# Sheet1.net
KiCad netlist of a schematic drawn in Altium Designer
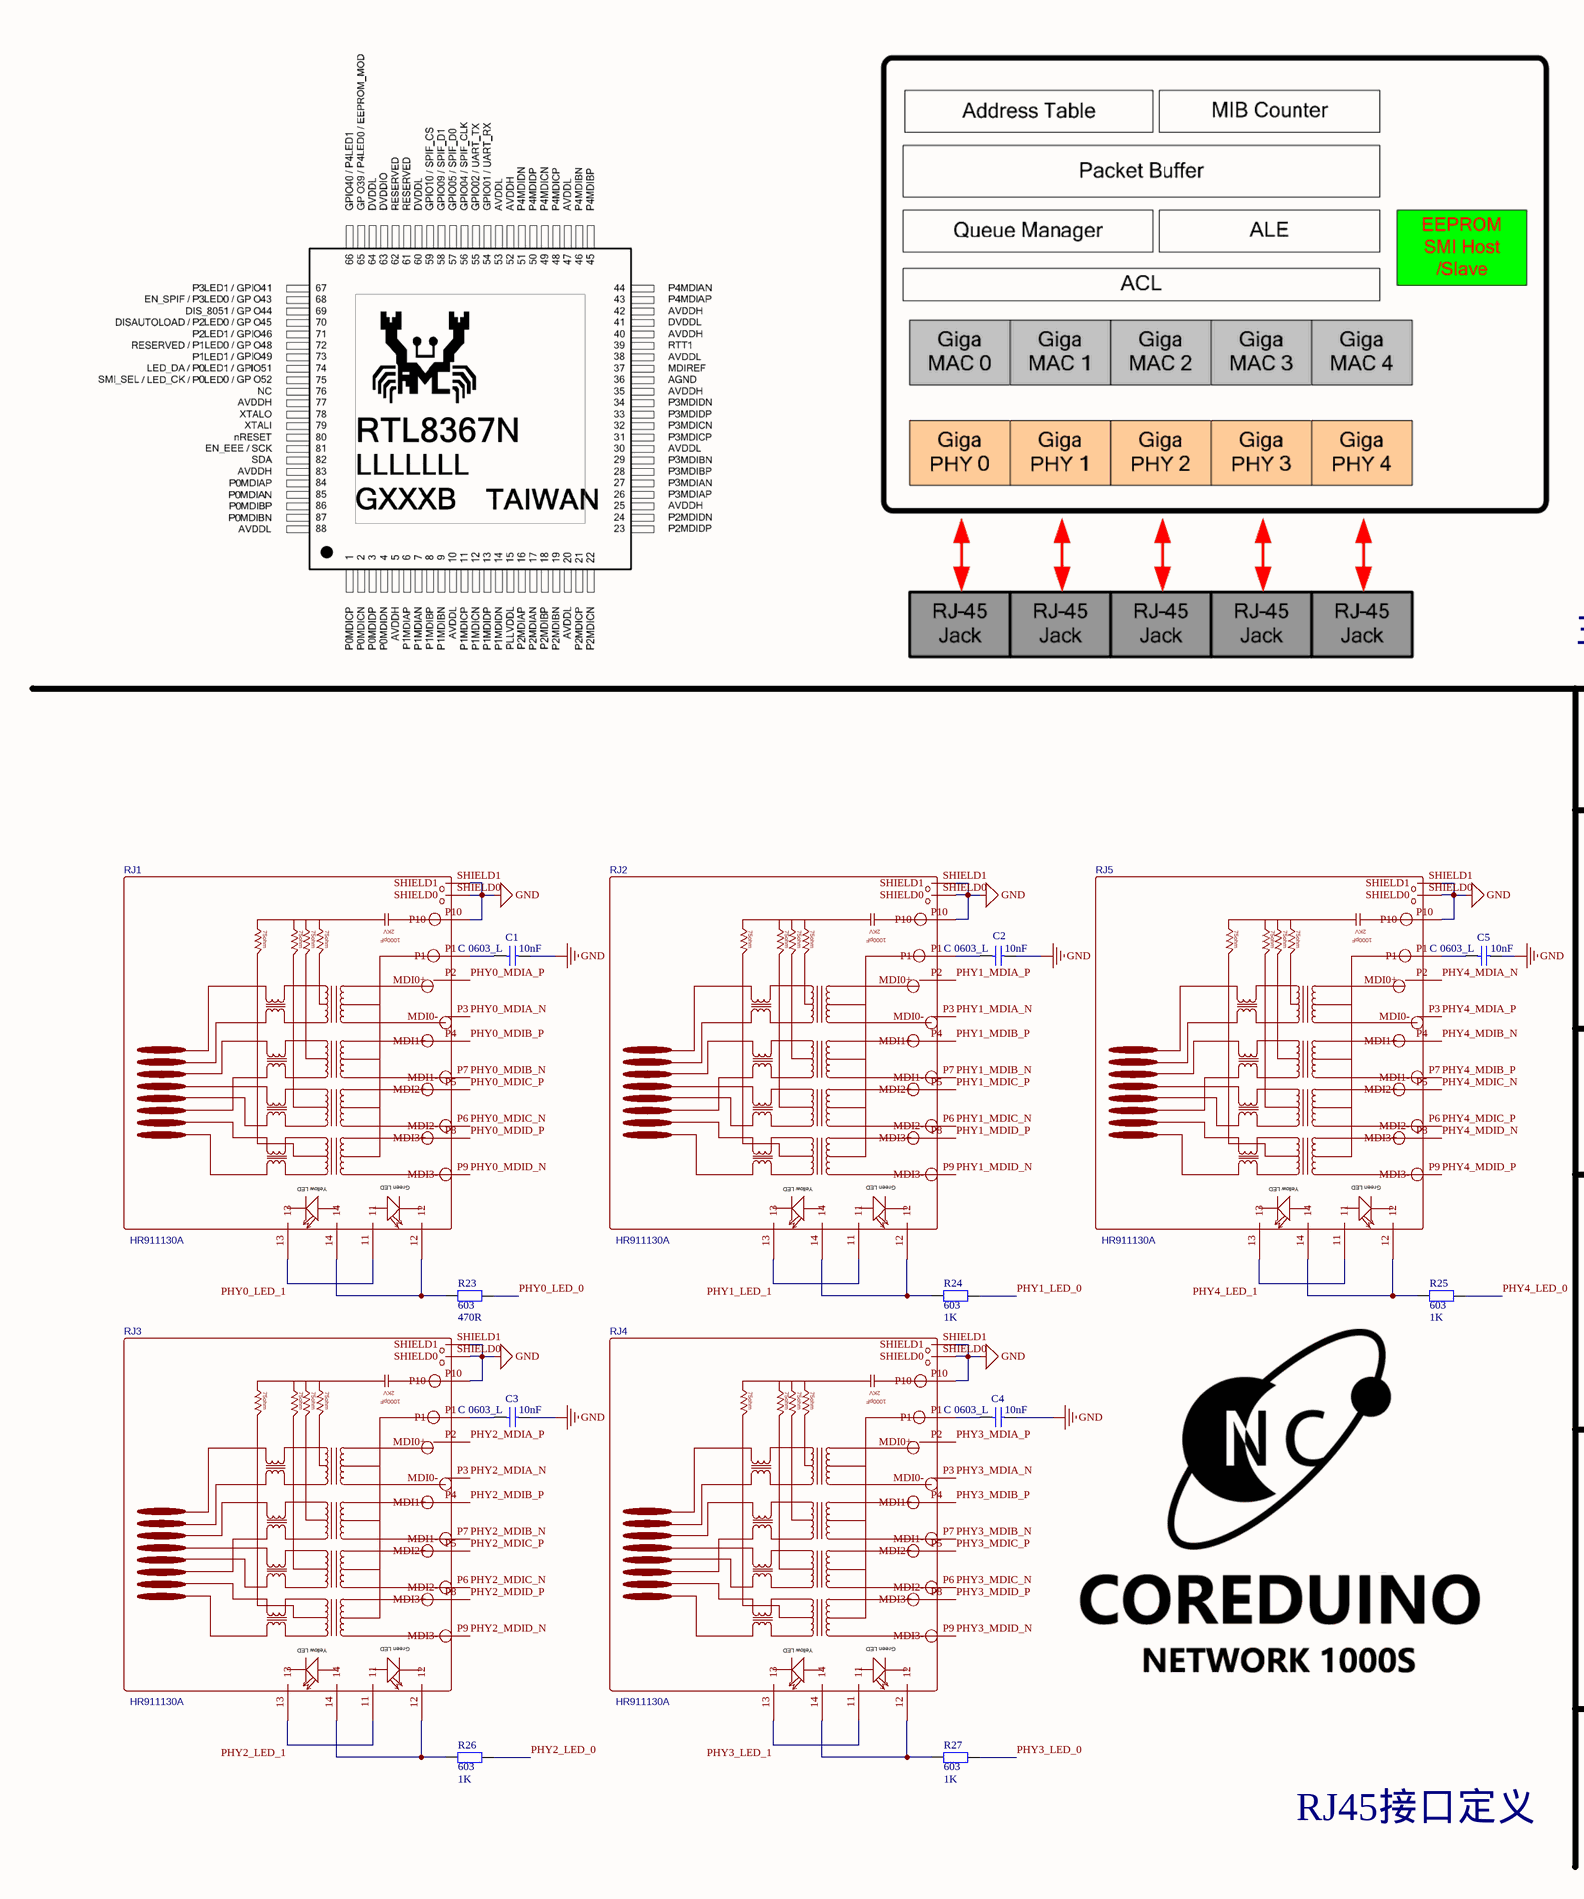
[diagram p0: Sheet1.SchDoc, left]
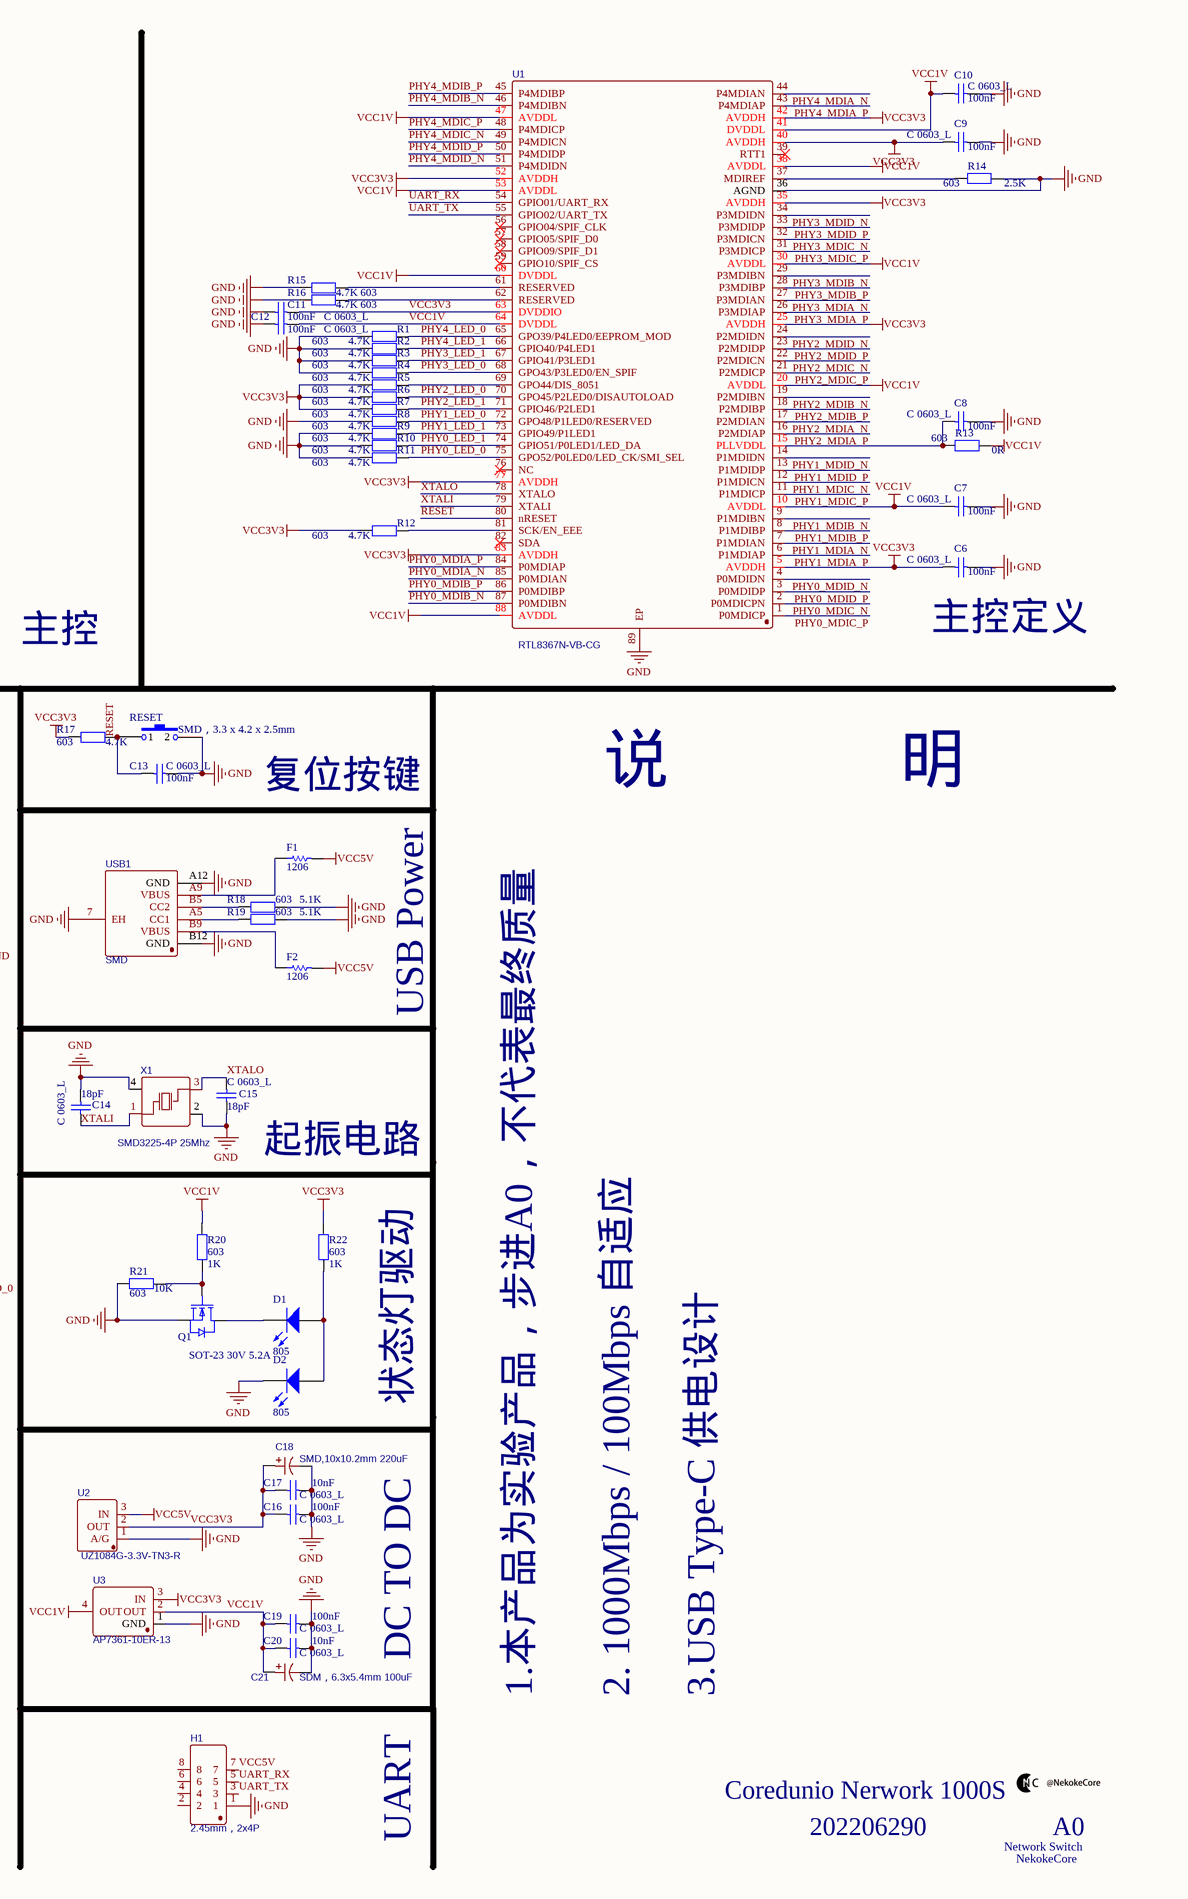
[diagram p1: Sheet1.SchDoc, right]

(export (version "E")
  (design (tool "Eeschema 10.0.6"))
  (components
    (comp (ref "C1")
      (value "C 0603_L")
      (footprint "C 0603_L")
      (description "贴片电容器（Capacitor）")
      (fields (field (name "ALTIUM_VALUE") "10nF") (field (name "PUBLISHER") "Altium Limited"))
      (libsource (lib "BaseLib") (part "C 0603_L"))
    )
    (comp (ref "C2")
      (value "C 0603_L")
      (footprint "C 0603_L")
      (description "贴片电容器（Capacitor）")
      (fields (field (name "ALTIUM_VALUE") "10nF") (field (name "PUBLISHER") "Altium Limited"))
      (libsource (lib "BaseLib") (part "C 0603_L"))
    )
    (comp (ref "C3")
      (value "C 0603_L")
      (footprint "C 0603_L")
      (description "贴片电容器（Capacitor）")
      (fields (field (name "ALTIUM_VALUE") "10nF") (field (name "PUBLISHER") "Altium Limited"))
      (libsource (lib "BaseLib") (part "C 0603_L"))
    )
    (comp (ref "C4")
      (value "C 0603_L")
      (footprint "C 0603_L")
      (description "贴片电容器（Capacitor）")
      (fields (field (name "ALTIUM_VALUE") "10nF") (field (name "PUBLISHER") "Altium Limited"))
      (libsource (lib "BaseLib") (part "C 0603_L"))
    )
    (comp (ref "C5")
      (value "C 0603_L")
      (footprint "C 0603_L")
      (description "贴片电容器（Capacitor）")
      (fields (field (name "ALTIUM_VALUE") "10nF") (field (name "PUBLISHER") "Altium Limited"))
      (libsource (lib "BaseLib") (part "C 0603_L"))
    )
    (comp (ref "C6")
      (value "C 0603_L")
      (footprint "C 0603_L")
      (description "贴片电容器（Capacitor）")
      (fields (field (name "ALTIUM_VALUE") "100nF") (field (name "PUBLISHER") "Altium Limited"))
      (libsource (lib "BaseLib") (part "C 0603_L"))
    )
    (comp (ref "C7")
      (value "C 0603_L")
      (footprint "C 0603_L")
      (description "贴片电容器（Capacitor）")
      (fields (field (name "ALTIUM_VALUE") "100nF") (field (name "PUBLISHER") "Altium Limited"))
      (libsource (lib "BaseLib") (part "C 0603_L"))
    )
    (comp (ref "C8")
      (value "C 0603_L")
      (footprint "C 0603_L")
      (description "贴片电容器（Capacitor）")
      (fields (field (name "ALTIUM_VALUE") "100nF") (field (name "PUBLISHER") "Altium Limited"))
      (libsource (lib "BaseLib") (part "C 0603_L"))
    )
    (comp (ref "C9")
      (value "C 0603_L")
      (footprint "C 0603_L")
      (description "贴片电容器（Capacitor）")
      (fields (field (name "ALTIUM_VALUE") "100nF") (field (name "PUBLISHER") "Altium Limited"))
      (libsource (lib "BaseLib") (part "C 0603_L"))
    )
    (comp (ref "C10")
      (value "C 0603_L")
      (footprint "C 0603_L")
      (description "贴片电容器（Capacitor）")
      (fields (field (name "ALTIUM_VALUE") "100nF") (field (name "PUBLISHER") "Altium Limited"))
      (libsource (lib "BaseLib") (part "C 0603_L"))
    )
    (comp (ref "C11")
      (value "C 0603_L")
      (footprint "C 0603_L")
      (description "贴片电容器（Capacitor）")
      (fields (field (name "ALTIUM_VALUE") "100nF") (field (name "PUBLISHER") "Altium Limited"))
      (libsource (lib "BaseLib") (part "C 0603_L"))
    )
    (comp (ref "C12")
      (value "C 0603_L")
      (footprint "C 0603_L")
      (description "贴片电容器（Capacitor）")
      (fields (field (name "ALTIUM_VALUE") "100nF") (field (name "PUBLISHER") "Altium Limited"))
      (libsource (lib "BaseLib") (part "C 0603_L"))
    )
    (comp (ref "C13")
      (value "C 0603_L")
      (footprint "C 0603_L")
      (description "贴片电容器（Capacitor）")
      (fields (field (name "ALTIUM_VALUE") "100nF") (field (name "PUBLISHER") "Altium Limited"))
      (libsource (lib "BaseLib") (part "C 0603_L"))
    )
    (comp (ref "C14")
      (value "C 0603_L")
      (footprint "C 0603_L")
      (description "贴片电容器（Capacitor）")
      (fields (field (name "ALTIUM_VALUE") "18pF") (field (name "PUBLISHER") "Altium Limited"))
      (libsource (lib "BaseLib") (part "C 0603_L"))
    )
    (comp (ref "C15")
      (value "C 0603_L")
      (footprint "C 0603_L")
      (description "贴片电容器（Capacitor）")
      (fields (field (name "ALTIUM_VALUE") "18pF") (field (name "PUBLISHER") "Altium Limited"))
      (libsource (lib "BaseLib") (part "C 0603_L"))
    )
    (comp (ref "C16")
      (value "C 0603_L")
      (footprint "C 0603_L")
      (description "贴片电容器（Capacitor）")
      (fields (field (name "ALTIUM_VALUE") "100nF") (field (name "PUBLISHER") "Altium Limited"))
      (libsource (lib "BaseLib") (part "C 0603_L"))
    )
    (comp (ref "C17")
      (value "C 0603_L")
      (footprint "C 0603_L")
      (description "贴片电容器（Capacitor）")
      (fields (field (name "ALTIUM_VALUE") "10nF") (field (name "PUBLISHER") "Altium Limited"))
      (libsource (lib "BaseLib") (part "C 0603_L"))
    )
    (comp (ref "C18")
      (value "SMD,10x10.2mm 220uF")
      (footprint "CAP-SMD_BD10.0-L10.3-W10.3-LS11.0-FD")
      (description "贴片铝电解电容器（Capacitor）")
      (fields
        (field (name "BOM_SUPPLIER PART") "C2887271")
        (field (name "BOM_MANUFACTURER PART") "RVT220UF50V67RV0021")
        (field (name "CONTRIBUTOR") "LCSC")
      )
      (libsource (lib "BaseLib") (part "RVT220UF50V67RV0021"))
    )
    (comp (ref "C19")
      (value "C 0603_L")
      (footprint "C 0603_L")
      (description "贴片电容器（Capacitor）")
      (fields (field (name "ALTIUM_VALUE") "100nF") (field (name "PUBLISHER") "Altium Limited"))
      (libsource (lib "BaseLib") (part "C 0603_L"))
    )
    (comp (ref "C20")
      (value "C 0603_L")
      (footprint "C 0603_L")
      (description "贴片电容器（Capacitor）")
      (fields (field (name "ALTIUM_VALUE") "10nF") (field (name "PUBLISHER") "Altium Limited"))
      (libsource (lib "BaseLib") (part "C 0603_L"))
    )
    (comp (ref "C21")
      (value "SDM，6.3x5.4mm 100uF")
      (footprint "CAP-SMD_BD6.3-L6.6-W6.6-LS7.2-FD")
      (description "贴片铝电解电容器（Capacitor）")
      (fields
        (field (name "BOM_SUPPLIER PART") "C2887276")
        (field (name "BOM_MANUFACTURER PART") "RVT100UF16V67RV0016")
        (field (name "CONTRIBUTOR") "LCSC")
      )
      (libsource (lib "BaseLib") (part "RVT100UF16V67RV0016"))
    )
    (comp (ref "D1")
      (value "805")
      (footprint "LED 0805G")
      (description "贴片发光二极管（LED）")
      (fields (field (name "PUBLISHER") "Altium Limited"))
      (libsource (lib "BaseLib") (part "LED 0805G 绿"))
    )
    (comp (ref "D2")
      (value "805")
      (footprint "LED 0805G")
      (description "贴片发光二极管（LED）")
      (fields (field (name "PUBLISHER") "Altium Limited"))
      (libsource (lib "BaseLib") (part "LED 0805G 绿"))
    )
    (comp (ref "F1")
      (value "1206")
      (footprint "FU 1206")
      (description "自恢复保险丝（Fuse）")
      (fields (field (name "PUBLISHER") "Altium Limited"))
      (libsource (lib "BaseLib") (part "nsmd150"))
    )
    (comp (ref "F2")
      (value "1206")
      (footprint "FU 1206")
      (description "自恢复保险丝（Fuse）")
      (fields (field (name "PUBLISHER") "Altium Limited"))
      (libsource (lib "BaseLib") (part "nsmd150"))
    )
    (comp (ref "H1")
      (value "2.45mm，2x4P")
      (footprint "HDR-TH_8P-P2.00-V-M-R2-C4-S2.00-2")
      (description "排针（Pin Jack）")
      (fields
        (field (name "BOM_SUPPLIER PART") "C2827500")
        (field (name "BOM_MANUFACTURER PART") "PH-01519")
        (field (name "CONTRIBUTOR") "LCSC")
      )
      (libsource (lib "BaseLib") (part "PH-01519"))
    )
    (comp (ref "Q1")
      (value "SOT-23 30V 5.2A")
      (footprint "AO3400A")
      (description "场效应管（MOSFET）")
      (fields (field (name "MANUFACTURER") "Nexperia(安世)") (field (name "MANUFACTURER PART") "2N7002,215"))
      (libsource (lib "BaseLib") (part "AO3400A"))
    )
    (comp (ref "R1")
      (value "603")
      (footprint "R 0603_L")
      (description "贴片电阻（Resistor）")
      (fields (field (name "ALTIUM_VALUE") "4.7K") (field (name "PUBLISHER") "Altium Limited"))
      (libsource (lib "BaseLib") (part "R 0603_L"))
    )
    (comp (ref "R2")
      (value "603")
      (footprint "R 0603_L")
      (description "贴片电阻（Resistor）")
      (fields (field (name "ALTIUM_VALUE") "4.7K") (field (name "PUBLISHER") "Altium Limited"))
      (libsource (lib "BaseLib") (part "R 0603_L"))
    )
    (comp (ref "R3")
      (value "603")
      (footprint "R 0603_L")
      (description "贴片电阻（Resistor）")
      (fields (field (name "ALTIUM_VALUE") "4.7K") (field (name "PUBLISHER") "Altium Limited"))
      (libsource (lib "BaseLib") (part "R 0603_L"))
    )
    (comp (ref "R4")
      (value "603")
      (footprint "R 0603_L")
      (description "贴片电阻（Resistor）")
      (fields (field (name "ALTIUM_VALUE") "4.7K") (field (name "PUBLISHER") "Altium Limited"))
      (libsource (lib "BaseLib") (part "R 0603_L"))
    )
    (comp (ref "R5")
      (value "603")
      (footprint "R 0603_L")
      (description "贴片电阻（Resistor）")
      (fields (field (name "ALTIUM_VALUE") "4.7K") (field (name "PUBLISHER") "Altium Limited"))
      (libsource (lib "BaseLib") (part "R 0603_L"))
    )
    (comp (ref "R6")
      (value "603")
      (footprint "R 0603_L")
      (description "贴片电阻（Resistor）")
      (fields (field (name "ALTIUM_VALUE") "4.7K") (field (name "PUBLISHER") "Altium Limited"))
      (libsource (lib "BaseLib") (part "R 0603_L"))
    )
    (comp (ref "R7")
      (value "603")
      (footprint "R 0603_L")
      (description "贴片电阻（Resistor）")
      (fields (field (name "ALTIUM_VALUE") "4.7K") (field (name "PUBLISHER") "Altium Limited"))
      (libsource (lib "BaseLib") (part "R 0603_L"))
    )
    (comp (ref "R8")
      (value "603")
      (footprint "R 0603_L")
      (description "贴片电阻（Resistor）")
      (fields (field (name "ALTIUM_VALUE") "4.7K") (field (name "PUBLISHER") "Altium Limited"))
      (libsource (lib "BaseLib") (part "R 0603_L"))
    )
    (comp (ref "R9")
      (value "603")
      (footprint "R 0603_L")
      (description "贴片电阻（Resistor）")
      (fields (field (name "ALTIUM_VALUE") "4.7K") (field (name "PUBLISHER") "Altium Limited"))
      (libsource (lib "BaseLib") (part "R 0603_L"))
    )
    (comp (ref "R10")
      (value "603")
      (footprint "R 0603_L")
      (description "贴片电阻（Resistor）")
      (fields (field (name "ALTIUM_VALUE") "4.7K") (field (name "PUBLISHER") "Altium Limited"))
      (libsource (lib "BaseLib") (part "R 0603_L"))
    )
    (comp (ref "R11")
      (value "603")
      (footprint "R 0603_L")
      (description "贴片电阻（Resistor）")
      (fields (field (name "ALTIUM_VALUE") "4.7K") (field (name "PUBLISHER") "Altium Limited"))
      (libsource (lib "BaseLib") (part "R 0603_L"))
    )
    (comp (ref "R12")
      (value "603")
      (footprint "R 0603_L")
      (description "贴片电阻（Resistor）")
      (fields (field (name "ALTIUM_VALUE") "4.7K") (field (name "PUBLISHER") "Altium Limited"))
      (libsource (lib "BaseLib") (part "R 0603_L"))
    )
    (comp (ref "R13")
      (value "603")
      (footprint "R 0603_L")
      (description "贴片电阻（Resistor）")
      (fields (field (name "ALTIUM_VALUE") "0R") (field (name "PUBLISHER") "Altium Limited"))
      (libsource (lib "BaseLib") (part "R 0603_L"))
    )
    (comp (ref "R14")
      (value "603")
      (footprint "R 0603_L")
      (description "贴片电阻（Resistor）")
      (fields (field (name "ALTIUM_VALUE") "2.5K") (field (name "PUBLISHER") "Altium Limited"))
      (libsource (lib "BaseLib") (part "R 0603_L"))
    )
    (comp (ref "R15")
      (value "603")
      (footprint "R 0603_L")
      (description "贴片电阻（Resistor）")
      (fields (field (name "ALTIUM_VALUE") "4.7K") (field (name "PUBLISHER") "Altium Limited"))
      (libsource (lib "BaseLib") (part "R 0603_L"))
    )
    (comp (ref "R16")
      (value "603")
      (footprint "R 0603_L")
      (description "贴片电阻（Resistor）")
      (fields (field (name "ALTIUM_VALUE") "4.7K") (field (name "PUBLISHER") "Altium Limited"))
      (libsource (lib "BaseLib") (part "R 0603_L"))
    )
    (comp (ref "R17")
      (value "603")
      (footprint "R 0603_L")
      (description "贴片电阻（Resistor）")
      (fields (field (name "ALTIUM_VALUE") "4.7K") (field (name "PUBLISHER") "Altium Limited"))
      (libsource (lib "BaseLib") (part "R 0603_L"))
    )
    (comp (ref "R18")
      (value "603")
      (footprint "R 0603_L")
      (description "贴片电阻（Resistor）")
      (fields (field (name "ALTIUM_VALUE") "5.1K") (field (name "PUBLISHER") "Altium Limited"))
      (libsource (lib "BaseLib") (part "R 0603_L"))
    )
    (comp (ref "R19")
      (value "603")
      (footprint "R 0603_L")
      (description "贴片电阻（Resistor）")
      (fields (field (name "ALTIUM_VALUE") "5.1K") (field (name "PUBLISHER") "Altium Limited"))
      (libsource (lib "BaseLib") (part "R 0603_L"))
    )
    (comp (ref "R20")
      (value "603")
      (footprint "R 0603_L")
      (description "贴片电阻（Resistor）")
      (fields (field (name "ALTIUM_VALUE") "1K") (field (name "PUBLISHER") "Altium Limited"))
      (libsource (lib "") (part "R 0603_L_1"))
    )
    (comp (ref "R21")
      (value "603")
      (footprint "R 0603_L")
      (description "贴片电阻（Resistor）")
      (fields (field (name "ALTIUM_VALUE") "10K") (field (name "PUBLISHER") "Altium Limited"))
      (libsource (lib "BaseLib") (part "R 0603_L"))
    )
    (comp (ref "R22")
      (value "603")
      (footprint "R 0603_L")
      (description "贴片电阻（Resistor）")
      (fields (field (name "ALTIUM_VALUE") "1K") (field (name "PUBLISHER") "Altium Limited"))
      (libsource (lib "") (part "R 0603_L_1"))
    )
    (comp (ref "R23")
      (value "603")
      (footprint "R 0603_L")
      (description "贴片电阻（Resistor）")
      (fields (field (name "ALTIUM_VALUE") "470R") (field (name "PUBLISHER") "Altium Limited"))
      (libsource (lib "BaseLib") (part "R 0603_L"))
    )
    (comp (ref "R24")
      (value "603")
      (footprint "R 0603_L")
      (description "贴片电阻（Resistor）")
      (fields (field (name "ALTIUM_VALUE") "1K") (field (name "PUBLISHER") "Altium Limited"))
      (libsource (lib "BaseLib") (part "R 0603_L"))
    )
    (comp (ref "R25")
      (value "603")
      (footprint "R 0603_L")
      (description "贴片电阻（Resistor）")
      (fields (field (name "ALTIUM_VALUE") "1K") (field (name "PUBLISHER") "Altium Limited"))
      (libsource (lib "BaseLib") (part "R 0603_L"))
    )
    (comp (ref "R26")
      (value "603")
      (footprint "R 0603_L")
      (description "贴片电阻（Resistor）")
      (fields (field (name "ALTIUM_VALUE") "1K") (field (name "PUBLISHER") "Altium Limited"))
      (libsource (lib "BaseLib") (part "R 0603_L"))
    )
    (comp (ref "R27")
      (value "603")
      (footprint "R 0603_L")
      (description "贴片电阻（Resistor）")
      (fields (field (name "ALTIUM_VALUE") "1K") (field (name "PUBLISHER") "Altium Limited"))
      (libsource (lib "BaseLib") (part "R 0603_L"))
    )
    (comp (ref "RESET")
      (value "SMD，3.3 x 4.2 x 2.5mm")
      (footprint "SMD-3.2*4.2")
      (description "轻触开关（Touch Switch）")
      (fields (field (name "PUBLISHER") "Altium Limited"))
      (libsource (lib "BaseLib") (part "260GF"))
    )
    (comp (ref "RJ1")
      (value "HR911130A")
      (footprint "RJ45-TH_HR911130A")
      (description "单插带灯以太网接口（RJ45）")
      (fields (field (name "BOM_SUPPLIER PART") "C54408"))
      (libsource (lib "BaseLib") (part "HR911130A"))
    )
    (comp (ref "RJ2")
      (value "HR911130A")
      (footprint "RJ45-TH_HR911130A")
      (description "单插带灯以太网接口（RJ45）")
      (fields (field (name "BOM_SUPPLIER PART") "C54408"))
      (libsource (lib "BaseLib") (part "HR911130A"))
    )
    (comp (ref "RJ3")
      (value "HR911130A")
      (footprint "RJ45-TH_HR911130A")
      (description "单插带灯以太网接口（RJ45）")
      (fields (field (name "BOM_SUPPLIER PART") "C54408"))
      (libsource (lib "BaseLib") (part "HR911130A"))
    )
    (comp (ref "RJ4")
      (value "HR911130A")
      (footprint "RJ45-TH_HR911130A")
      (description "单插带灯以太网接口（RJ45）")
      (fields (field (name "BOM_SUPPLIER PART") "C54408"))
      (libsource (lib "BaseLib") (part "HR911130A"))
    )
    (comp (ref "RJ5")
      (value "HR911130A")
      (footprint "RJ45-TH_HR911130A")
      (description "单插带灯以太网接口（RJ45）")
      (fields (field (name "BOM_SUPPLIER PART") "C54408"))
      (libsource (lib "BaseLib") (part "HR911130A"))
    )
    (comp (ref "U1")
      (value "RTL8367N-VB-CG")
      (footprint "MQFN-88_L10.0-W10.0-P0.40-BL-EP8.5")
      (description "以太网芯片（Network）")
      (fields (field (name "BOM_SUPPLIER PART") "C2760851") (field (name "CONTRIBUTOR") "LCSC"))
      (libsource (lib "BaseLib") (part "RTL8367N-VB-CG"))
    )
    (comp (ref "U2")
      (value "UZ1084G-3.3V-TN3-R")
      (footprint "TO-252-3_L6.5-W5.8-P4.58-TL")
      (description "线性稳压器（LDO）")
      (fields (field (name "BOM_SUPPLIER PART") "C84897"))
      (libsource (lib "BaseLib") (part "UZ1084G-3.3V-TN3-R"))
    )
    (comp (ref "U3")
      (value "AP7361-10ER-13")
      (footprint "SOT-223_L6.5-W3.5-P2.30-LS7.0-BR")
      (description "线性稳压器（LDO）")
      (fields (field (name "BOM_SUPPLIER PART") "C460389") (field (name "CONTRIBUTOR") "LCSC"))
      (libsource (lib "BaseLib") (part "AP7361-10ER-13"))
    )
    (comp (ref "USB1")
      (value "SMD")
      (footprint "TYPE-C-SMD_TYPE-C-6P")
      (description "通用通信总线接口（USB）")
      (fields
        (field (name "BOM_SUPPLIER PART") "C456012")
        (field (name "BOM_MANUFACTURER PART") "TYPE-C 6P")
        (field (name "CONTRIBUTOR") "LCSC")
      )
      (libsource (lib "BaseLib") (part "TYPE-C 6P QT"))
    )
    (comp (ref "X1")
      (value "SMD3225-4P 25Mhz")
      (footprint "OSC-SMD_4P-L3.2-W2.5-BL")
      (description "无源晶振（Crystal）")
      (fields
        (field (name "BOM_SUPPLIER PART") "C117869")
        (field (name "BOM_MANUFACTURER PART") "XXCEELNANF-25MHZ")
        (field (name "CONTRIBUTOR") "LCSC")
      )
      (libsource (lib "BaseLib") (part "XXCEELNANF-25MHZ"))
    )
  )
  (nets
    (net (code "1") (name "/PHY0_LED_0") (class "Default")
      (node (ref "R11") (pin "2") (pinfunction "2_2") (pintype "passive"))
      (node (ref "R23") (pin "2") (pinfunction "2_2") (pintype "passive"))
      (node (ref "U1") (pin "75") (pinfunction "GPO52/P0LED0/LED_CK/SMI_SEL_75") (pintype "passive"))
    )
    (net (code "2") (name "/PHY0_LED_1") (class "Default")
      (node (ref "R10") (pin "2") (pinfunction "2_2") (pintype "passive"))
      (node (ref "RJ1") (pin "11") (pinfunction "11_11") (pintype "passive"))
      (node (ref "RJ1") (pin "13") (pinfunction "13_13") (pintype "passive"))
      (node (ref "U1") (pin "74") (pinfunction "GPIO51/P0LED1/LED_DA_74") (pintype "passive"))
    )
    (net (code "3") (name "/PHY0_MDIA_N") (class "Default")
      (node (ref "RJ1") (pin "P3") (pinfunction "MDI0-_P3") (pintype "passive"))
      (node (ref "U1") (pin "85") (pinfunction "P0MDIAN_85") (pintype "passive"))
    )
    (net (code "4") (name "/PHY0_MDIA_P") (class "Default")
      (node (ref "RJ1") (pin "P2") (pinfunction "MDI0+_P2") (pintype "passive"))
      (node (ref "U1") (pin "84") (pinfunction "P0MDIAP_84") (pintype "passive"))
    )
    (net (code "5") (name "/PHY0_MDIB_N") (class "Default")
      (node (ref "RJ1") (pin "P7") (pinfunction "MDI1-_P7") (pintype "passive"))
      (node (ref "U1") (pin "87") (pinfunction "P0MDIBN_87") (pintype "passive"))
    )
    (net (code "6") (name "/PHY0_MDIB_P") (class "Default")
      (node (ref "RJ1") (pin "P4") (pinfunction "MDI1+_P4") (pintype "passive"))
      (node (ref "U1") (pin "86") (pinfunction "P0MDIBP_86") (pintype "passive"))
    )
    (net (code "7") (name "/PHY0_MDIC_N") (class "Default")
      (node (ref "RJ1") (pin "P6") (pinfunction "MDI2-_P6") (pintype "passive"))
      (node (ref "U1") (pin "2") (pinfunction "P0MDICPN_2") (pintype "passive"))
    )
    (net (code "8") (name "/PHY0_MDIC_P") (class "Default")
      (node (ref "RJ1") (pin "P5") (pinfunction "MDI2+_P5") (pintype "passive"))
      (node (ref "U1") (pin "1") (pinfunction "P0MDICP_1") (pintype "passive"))
    )
    (net (code "9") (name "/PHY0_MDID_N") (class "Default")
      (node (ref "RJ1") (pin "P9") (pinfunction "MDI3-_P9") (pintype "passive"))
      (node (ref "U1") (pin "4") (pinfunction "P0MDIDN_4") (pintype "passive"))
    )
    (net (code "10") (name "/PHY0_MDID_P") (class "Default")
      (node (ref "RJ1") (pin "P8") (pinfunction "MDI3+_P8") (pintype "passive"))
      (node (ref "U1") (pin "3") (pinfunction "P0MDIDP_3") (pintype "passive"))
    )
    (net (code "11") (name "/PHY1_LED_0") (class "Default")
      (node (ref "R24") (pin "2") (pinfunction "2_2") (pintype "passive"))
      (node (ref "R8") (pin "2") (pinfunction "2_2") (pintype "passive"))
      (node (ref "U1") (pin "72") (pinfunction "GPO48/P1LED0/RESERVED_72") (pintype "passive"))
    )
    (net (code "12") (name "/PHY1_LED_1") (class "Default")
      (node (ref "R9") (pin "2") (pinfunction "2_2") (pintype "passive"))
      (node (ref "RJ2") (pin "11") (pinfunction "11_11") (pintype "passive"))
      (node (ref "RJ2") (pin "13") (pinfunction "13_13") (pintype "passive"))
      (node (ref "U1") (pin "73") (pinfunction "GPIO49/P1LED1_73") (pintype "passive"))
    )
    (net (code "13") (name "/PHY1_MDIA_N") (class "Default")
      (node (ref "RJ2") (pin "P3") (pinfunction "MDI0-_P3") (pintype "passive"))
      (node (ref "U1") (pin "7") (pinfunction "P1MDIAN_7") (pintype "passive"))
    )
    (net (code "14") (name "/PHY1_MDIA_P") (class "Default")
      (node (ref "RJ2") (pin "P2") (pinfunction "MDI0+_P2") (pintype "passive"))
      (node (ref "U1") (pin "6") (pinfunction "P1MDIAP_6") (pintype "passive"))
    )
    (net (code "15") (name "/PHY1_MDIB_N") (class "Default")
      (node (ref "RJ2") (pin "P7") (pinfunction "MDI1-_P7") (pintype "passive"))
      (node (ref "U1") (pin "9") (pinfunction "P1MDIBN_9") (pintype "passive"))
    )
    (net (code "16") (name "/PHY1_MDIB_P") (class "Default")
      (node (ref "RJ2") (pin "P4") (pinfunction "MDI1+_P4") (pintype "passive"))
      (node (ref "U1") (pin "8") (pinfunction "P1MDIBP_8") (pintype "passive"))
    )
    (net (code "17") (name "/PHY1_MDIC_N") (class "Default")
      (node (ref "RJ2") (pin "P6") (pinfunction "MDI2-_P6") (pintype "passive"))
      (node (ref "U1") (pin "12") (pinfunction "P1MDICN_12") (pintype "passive"))
    )
    (net (code "18") (name "/PHY1_MDIC_P") (class "Default")
      (node (ref "RJ2") (pin "P5") (pinfunction "MDI2+_P5") (pintype "passive"))
      (node (ref "U1") (pin "11") (pinfunction "P1MDICP_11") (pintype "passive"))
    )
    (net (code "19") (name "/PHY1_MDID_N") (class "Default")
      (node (ref "RJ2") (pin "P9") (pinfunction "MDI3-_P9") (pintype "passive"))
      (node (ref "U1") (pin "14") (pinfunction "P1MDIDN_14") (pintype "passive"))
    )
    (net (code "20") (name "/PHY1_MDID_P") (class "Default")
      (node (ref "RJ2") (pin "P8") (pinfunction "MDI3+_P8") (pintype "passive"))
      (node (ref "U1") (pin "13") (pinfunction "P1MDIDP_13") (pintype "passive"))
    )
    (net (code "21") (name "/PHY2_LED_0") (class "Default")
      (node (ref "R26") (pin "2") (pinfunction "2_2") (pintype "passive"))
      (node (ref "R6") (pin "2") (pinfunction "2_2") (pintype "passive"))
      (node (ref "U1") (pin "70") (pinfunction "GPO45/P2LED0/DISAUTOLOAD_70") (pintype "passive"))
    )
    (net (code "22") (name "/PHY2_LED_1") (class "Default")
      (node (ref "R7") (pin "2") (pinfunction "2_2") (pintype "passive"))
      (node (ref "RJ3") (pin "11") (pinfunction "11_11") (pintype "passive"))
      (node (ref "RJ3") (pin "13") (pinfunction "13_13") (pintype "passive"))
      (node (ref "U1") (pin "71") (pinfunction "GPIO46/P2LED1_71") (pintype "passive"))
    )
    (net (code "23") (name "/PHY2_MDIA_N") (class "Default")
      (node (ref "RJ3") (pin "P3") (pinfunction "MDI0-_P3") (pintype "passive"))
      (node (ref "U1") (pin "17") (pinfunction "P2MDIAN_17") (pintype "passive"))
    )
    (net (code "24") (name "/PHY2_MDIA_P") (class "Default")
      (node (ref "RJ3") (pin "P2") (pinfunction "MDI0+_P2") (pintype "passive"))
      (node (ref "U1") (pin "16") (pinfunction "P2MDIAP_16") (pintype "passive"))
    )
    (net (code "25") (name "/PHY2_MDIB_N") (class "Default")
      (node (ref "RJ3") (pin "P7") (pinfunction "MDI1-_P7") (pintype "passive"))
      (node (ref "U1") (pin "19") (pinfunction "P2MDIBN_19") (pintype "passive"))
    )
    (net (code "26") (name "/PHY2_MDIB_P") (class "Default")
      (node (ref "RJ3") (pin "P4") (pinfunction "MDI1+_P4") (pintype "passive"))
      (node (ref "U1") (pin "18") (pinfunction "P2MDIBP_18") (pintype "passive"))
    )
    (net (code "27") (name "/PHY2_MDIC_N") (class "Default")
      (node (ref "RJ3") (pin "P6") (pinfunction "MDI2-_P6") (pintype "passive"))
      (node (ref "U1") (pin "22") (pinfunction "P2MDICN_22") (pintype "passive"))
    )
    (net (code "28") (name "/PHY2_MDIC_P") (class "Default")
      (node (ref "RJ3") (pin "P5") (pinfunction "MDI2+_P5") (pintype "passive"))
      (node (ref "U1") (pin "21") (pinfunction "P2MDICP_21") (pintype "passive"))
    )
    (net (code "29") (name "/PHY2_MDID_N") (class "Default")
      (node (ref "RJ3") (pin "P9") (pinfunction "MDI3-_P9") (pintype "passive"))
      (node (ref "U1") (pin "24") (pinfunction "P2MDIDN_24") (pintype "passive"))
    )
    (net (code "30") (name "/PHY2_MDID_P") (class "Default")
      (node (ref "RJ3") (pin "P8") (pinfunction "MDI3+_P8") (pintype "passive"))
      (node (ref "U1") (pin "23") (pinfunction "P2MDIDP_23") (pintype "passive"))
    )
    (net (code "31") (name "/PHY3_LED_0") (class "Default")
      (node (ref "R27") (pin "2") (pinfunction "2_2") (pintype "passive"))
      (node (ref "R4") (pin "2") (pinfunction "2_2") (pintype "passive"))
      (node (ref "U1") (pin "68") (pinfunction "GPO43/P3LED0/EN_SPIF_68") (pintype "passive"))
    )
    (net (code "32") (name "/PHY3_LED_1") (class "Default")
      (node (ref "R3") (pin "2") (pinfunction "2_2") (pintype "passive"))
      (node (ref "RJ4") (pin "11") (pinfunction "11_11") (pintype "passive"))
      (node (ref "RJ4") (pin "13") (pinfunction "13_13") (pintype "passive"))
      (node (ref "U1") (pin "67") (pinfunction "GPIO41/P3LED1_67") (pintype "passive"))
    )
    (net (code "33") (name "/PHY3_MDIA_N") (class "Default")
      (node (ref "RJ4") (pin "P3") (pinfunction "MDI0-_P3") (pintype "passive"))
      (node (ref "U1") (pin "27") (pinfunction "P3MDIAN_27") (pintype "passive"))
    )
    (net (code "34") (name "/PHY3_MDIA_P") (class "Default")
      (node (ref "RJ4") (pin "P2") (pinfunction "MDI0+_P2") (pintype "passive"))
      (node (ref "U1") (pin "26") (pinfunction "P3MDIAP_26") (pintype "passive"))
    )
    (net (code "35") (name "/PHY3_MDIB_N") (class "Default")
      (node (ref "RJ4") (pin "P7") (pinfunction "MDI1-_P7") (pintype "passive"))
      (node (ref "U1") (pin "29") (pinfunction "P3MDIBN_29") (pintype "passive"))
    )
    (net (code "36") (name "/PHY3_MDIB_P") (class "Default")
      (node (ref "RJ4") (pin "P4") (pinfunction "MDI1+_P4") (pintype "passive"))
      (node (ref "U1") (pin "28") (pinfunction "P3MDIBP_28") (pintype "passive"))
    )
    (net (code "37") (name "/PHY3_MDIC_N") (class "Default")
      (node (ref "RJ4") (pin "P6") (pinfunction "MDI2-_P6") (pintype "passive"))
      (node (ref "U1") (pin "32") (pinfunction "P3MDICN_32") (pintype "passive"))
    )
    (net (code "38") (name "/PHY3_MDIC_P") (class "Default")
      (node (ref "RJ4") (pin "P5") (pinfunction "MDI2+_P5") (pintype "passive"))
      (node (ref "U1") (pin "31") (pinfunction "P3MDICP_31") (pintype "passive"))
    )
    (net (code "39") (name "/PHY3_MDID_N") (class "Default")
      (node (ref "RJ4") (pin "P9") (pinfunction "MDI3-_P9") (pintype "passive"))
      (node (ref "U1") (pin "34") (pinfunction "P3MDIDN_34") (pintype "passive"))
    )
    (net (code "40") (name "/PHY3_MDID_P") (class "Default")
      (node (ref "RJ4") (pin "P8") (pinfunction "MDI3+_P8") (pintype "passive"))
      (node (ref "U1") (pin "33") (pinfunction "P3MDIDP_33") (pintype "passive"))
    )
    (net (code "41") (name "/PHY4_LED_0") (class "Default")
      (node (ref "R1") (pin "2") (pinfunction "2_2") (pintype "passive"))
      (node (ref "R25") (pin "2") (pinfunction "2_2") (pintype "passive"))
      (node (ref "U1") (pin "65") (pinfunction "GPO39/P4LED0/EEPROM_MOD_65") (pintype "passive"))
    )
    (net (code "42") (name "/PHY4_LED_1") (class "Default")
      (node (ref "R2") (pin "2") (pinfunction "2_2") (pintype "passive"))
      (node (ref "RJ5") (pin "11") (pinfunction "11_11") (pintype "passive"))
      (node (ref "RJ5") (pin "13") (pinfunction "13_13") (pintype "passive"))
      (node (ref "U1") (pin "66") (pinfunction "GPIO40/P4LED1_66") (pintype "passive"))
    )
    (net (code "43") (name "/PHY4_MDIA_N") (class "Default")
      (node (ref "RJ5") (pin "P2") (pinfunction "MDI0+_P2") (pintype "passive"))
      (node (ref "U1") (pin "44") (pinfunction "P4MDIAN_44") (pintype "passive"))
    )
    (net (code "44") (name "/PHY4_MDIA_P") (class "Default")
      (node (ref "RJ5") (pin "P3") (pinfunction "MDI0-_P3") (pintype "passive"))
      (node (ref "U1") (pin "43") (pinfunction "P4MDIAP_43") (pintype "passive"))
    )
    (net (code "45") (name "/PHY4_MDIB_N") (class "Default")
      (node (ref "RJ5") (pin "P4") (pinfunction "MDI1+_P4") (pintype "passive"))
      (node (ref "U1") (pin "46") (pinfunction "P4MDIBN_46") (pintype "passive"))
    )
    (net (code "46") (name "/PHY4_MDIB_P") (class "Default")
      (node (ref "RJ5") (pin "P7") (pinfunction "MDI1-_P7") (pintype "passive"))
      (node (ref "U1") (pin "45") (pinfunction "P4MDIBP_45") (pintype "passive"))
    )
    (net (code "47") (name "/PHY4_MDIC_N") (class "Default")
      (node (ref "RJ5") (pin "P5") (pinfunction "MDI2+_P5") (pintype "passive"))
      (node (ref "U1") (pin "49") (pinfunction "P4MDICN_49") (pintype "passive"))
    )
    (net (code "48") (name "/PHY4_MDIC_P") (class "Default")
      (node (ref "RJ5") (pin "P6") (pinfunction "MDI2-_P6") (pintype "passive"))
      (node (ref "U1") (pin "48") (pinfunction "P4MDICP_48") (pintype "passive"))
    )
    (net (code "49") (name "/PHY4_MDID_N") (class "Default")
      (node (ref "RJ5") (pin "P8") (pinfunction "MDI3+_P8") (pintype "passive"))
      (node (ref "U1") (pin "51") (pinfunction "P4MDIDN_51") (pintype "passive"))
    )
    (net (code "50") (name "/PHY4_MDID_P") (class "Default")
      (node (ref "RJ5") (pin "P9") (pinfunction "MDI3-_P9") (pintype "passive"))
      (node (ref "U1") (pin "50") (pinfunction "P4MDIDP_50") (pintype "passive"))
    )
    (net (code "51") (name "/RESET") (class "Default")
      (node (ref "C13") (pin "1") (pinfunction "1_1") (pintype "passive"))
      (node (ref "R17") (pin "2") (pinfunction "2_2") (pintype "passive"))
      (node (ref "RESET") (pin "1") (pinfunction "1_1") (pintype "passive"))
      (node (ref "U1") (pin "80") (pinfunction "nRESET_80") (pintype "passive"))
    )
    (net (code "52") (name "/UART_RX") (class "Default")
      (node (ref "H1") (pin "5") (pinfunction "5_5") (pintype "passive"))
      (node (ref "U1") (pin "54") (pinfunction "GPIO01/UART_RX_54") (pintype "passive"))
    )
    (net (code "53") (name "/UART_TX") (class "Default")
      (node (ref "H1") (pin "3") (pinfunction "3_3") (pintype "passive"))
      (node (ref "U1") (pin "55") (pinfunction "GPIO02/UART_TX_55") (pintype "passive"))
    )
    (net (code "54") (name "/XTALI") (class "Default")
      (node (ref "C14") (pin "1") (pinfunction "1_1") (pintype "passive"))
      (node (ref "U1") (pin "79") (pinfunction "XTALI_79") (pintype "passive"))
      (node (ref "X1") (pin "1") (pinfunction "OSC1_1") (pintype "passive"))
    )
    (net (code "55") (name "/XTALO") (class "Default")
      (node (ref "C15") (pin "2") (pinfunction "2_2") (pintype "passive"))
      (node (ref "U1") (pin "78") (pinfunction "XTALO_78") (pintype "passive"))
      (node (ref "X1") (pin "3") (pinfunction "OSC2_3") (pintype "passive"))
    )
    (net (code "56") (name "GND") (class "Default")
      (node (ref "C1") (pin "2") (pinfunction "2_2") (pintype "passive"))
      (node (ref "C10") (pin "2") (pinfunction "2_2") (pintype "passive"))
      (node (ref "C11") (pin "1") (pinfunction "1_1") (pintype "passive"))
      (node (ref "C12") (pin "1") (pinfunction "1_1") (pintype "passive"))
      (node (ref "C13") (pin "2") (pinfunction "2_2") (pintype "passive"))
      (node (ref "C14") (pin "2") (pinfunction "2_2") (pintype "passive"))
      (node (ref "C15") (pin "1") (pinfunction "1_1") (pintype "passive"))
      (node (ref "C16") (pin "2") (pinfunction "2_2") (pintype "passive"))
      (node (ref "C17") (pin "2") (pinfunction "2_2") (pintype "passive"))
      (node (ref "C18") (pin "2") (pinfunction "2_2") (pintype "passive"))
      (node (ref "C19") (pin "2") (pinfunction "2_2") (pintype "passive"))
      (node (ref "C2") (pin "2") (pinfunction "2_2") (pintype "passive"))
      (node (ref "C20") (pin "2") (pinfunction "2_2") (pintype "passive"))
      (node (ref "C21") (pin "2") (pinfunction "2_2") (pintype "passive"))
      (node (ref "C3") (pin "2") (pinfunction "2_2") (pintype "passive"))
      (node (ref "C4") (pin "2") (pinfunction "2_2") (pintype "passive"))
      (node (ref "C5") (pin "2") (pinfunction "2_2") (pintype "passive"))
      (node (ref "C6") (pin "2") (pinfunction "2_2") (pintype "passive"))
      (node (ref "C7") (pin "2") (pinfunction "2_2") (pintype "passive"))
      (node (ref "C8") (pin "2") (pinfunction "2_2") (pintype "passive"))
      (node (ref "C9") (pin "2") (pinfunction "2_2") (pintype "passive"))
      (node (ref "D2") (pin "2") (pinfunction "K_2") (pintype "passive"))
      (node (ref "H1") (pin "1") (pinfunction "1_1") (pintype "passive"))
      (node (ref "Q1") (pin "2") (pinfunction "S_2") (pintype "passive"))
      (node (ref "R1") (pin "1") (pinfunction "1_1") (pintype "passive"))
      (node (ref "R10") (pin "1") (pinfunction "1_1") (pintype "passive"))
      (node (ref "R11") (pin "1") (pinfunction "1_1") (pintype "passive"))
      (node (ref "R14") (pin "2") (pinfunction "2_2") (pintype "passive"))
      (node (ref "R15") (pin "1") (pinfunction "1_1") (pintype "passive"))
      (node (ref "R16") (pin "1") (pinfunction "1_1") (pintype "passive"))
      (node (ref "R18") (pin "2") (pinfunction "2_2") (pintype "passive"))
      (node (ref "R19") (pin "2") (pinfunction "2_2") (pintype "passive"))
      (node (ref "R2") (pin "1") (pinfunction "1_1") (pintype "passive"))
      (node (ref "R21") (pin "1") (pinfunction "1_1") (pintype "passive"))
      (node (ref "R3") (pin "1") (pinfunction "1_1") (pintype "passive"))
      (node (ref "R4") (pin "1") (pinfunction "1_1") (pintype "passive"))
      (node (ref "R8") (pin "1") (pinfunction "1_1") (pintype "passive"))
      (node (ref "R9") (pin "1") (pinfunction "1_1") (pintype "passive"))
      (node (ref "RESET") (pin "2") (pinfunction "2_2") (pintype "passive"))
      (node (ref "RJ1") (pin "P10") (pinfunction "P10_P10") (pintype "passive"))
      (node (ref "RJ1") (pin "SHIELD0") (pinfunction "SHIELD0_SHIELD0") (pintype "passive"))
      (node (ref "RJ1") (pin "SHIELD1") (pinfunction "SHIELD1_SHIELD1") (pintype "passive"))
      (node (ref "RJ2") (pin "P10") (pinfunction "P10_P10") (pintype "passive"))
      (node (ref "RJ2") (pin "SHIELD0") (pinfunction "SHIELD0_SHIELD0") (pintype "passive"))
      (node (ref "RJ2") (pin "SHIELD1") (pinfunction "SHIELD1_SHIELD1") (pintype "passive"))
      (node (ref "RJ3") (pin "P10") (pinfunction "P10_P10") (pintype "passive"))
      (node (ref "RJ3") (pin "SHIELD0") (pinfunction "SHIELD0_SHIELD0") (pintype "passive"))
      (node (ref "RJ3") (pin "SHIELD1") (pinfunction "SHIELD1_SHIELD1") (pintype "passive"))
      (node (ref "RJ4") (pin "P10") (pinfunction "P10_P10") (pintype "passive"))
      (node (ref "RJ4") (pin "SHIELD0") (pinfunction "SHIELD0_SHIELD0") (pintype "passive"))
      (node (ref "RJ4") (pin "SHIELD1") (pinfunction "SHIELD1_SHIELD1") (pintype "passive"))
      (node (ref "RJ5") (pin "P10") (pinfunction "P10_P10") (pintype "passive"))
      (node (ref "RJ5") (pin "SHIELD0") (pinfunction "SHIELD0_SHIELD0") (pintype "passive"))
      (node (ref "RJ5") (pin "SHIELD1") (pinfunction "SHIELD1_SHIELD1") (pintype "passive"))
      (node (ref "U1") (pin "36") (pinfunction "AGND_36") (pintype "passive"))
      (node (ref "U1") (pin "89") (pinfunction "EP_89") (pintype "passive"))
      (node (ref "U2") (pin "1") (pinfunction "A/G_1") (pintype "passive"))
      (node (ref "U3") (pin "1") (pinfunction "GND_1") (pintype "passive"))
      (node (ref "USB1") (pin "7") (pinfunction "EH_7") (pintype "passive"))
      (node (ref "USB1") (pin "A12") (pinfunction "GND_A12") (pintype "passive"))
      (node (ref "USB1") (pin "B12") (pinfunction "GND_B12") (pintype "passive"))
      (node (ref "X1") (pin "2") (pinfunction "GND_2") (pintype "passive"))
      (node (ref "X1") (pin "4") (pinfunction "GND_4") (pintype "passive"))
    )
    (net (code "57") (name "Net-(C1-Pad1)") (class "Default")
      (node (ref "C1") (pin "1") (pinfunction "1_1") (pintype "passive"))
      (node (ref "RJ1") (pin "P1") (pinfunction "P1_P1") (pintype "passive"))
    )
    (net (code "58") (name "Net-(C2-Pad1)") (class "Default")
      (node (ref "C2") (pin "1") (pinfunction "1_1") (pintype "passive"))
      (node (ref "RJ2") (pin "P1") (pinfunction "P1_P1") (pintype "passive"))
    )
    (net (code "59") (name "Net-(C3-Pad1)") (class "Default")
      (node (ref "C3") (pin "1") (pinfunction "1_1") (pintype "passive"))
      (node (ref "RJ3") (pin "P1") (pinfunction "P1_P1") (pintype "passive"))
    )
    (net (code "60") (name "Net-(C4-Pad1)") (class "Default")
      (node (ref "C4") (pin "1") (pinfunction "1_1") (pintype "passive"))
      (node (ref "RJ4") (pin "P1") (pinfunction "P1_P1") (pintype "passive"))
    )
    (net (code "61") (name "Net-(C5-Pad1)") (class "Default")
      (node (ref "C5") (pin "1") (pinfunction "1_1") (pintype "passive"))
      (node (ref "RJ5") (pin "P1") (pinfunction "P1_P1") (pintype "passive"))
    )
    (net (code "62") (name "Net-(D1-A)") (class "Default")
      (node (ref "D1") (pin "1") (pinfunction "A_1") (pintype "passive"))
      (node (ref "D2") (pin "1") (pinfunction "A_1") (pintype "passive"))
      (node (ref "R22") (pin "1") (pinfunction "1_1") (pintype "passive"))
    )
    (net (code "63") (name "Net-(D1-K)") (class "Default")
      (node (ref "D1") (pin "2") (pinfunction "K_2") (pintype "passive"))
      (node (ref "Q1") (pin "3") (pinfunction "D_3") (pintype "passive"))
    )
    (net (code "64") (name "Net-(F1-Pad1)") (class "Default")
      (node (ref "F1") (pin "1") (pinfunction "1_1") (pintype "passive"))
      (node (ref "USB1") (pin "A9") (pinfunction "VBUS_A9") (pintype "passive"))
    )
    (net (code "65") (name "Net-(F2-Pad1)") (class "Default")
      (node (ref "F2") (pin "1") (pinfunction "1_1") (pintype "passive"))
      (node (ref "USB1") (pin "B9") (pinfunction "VBUS_B9") (pintype "passive"))
    )
    (net (code "66") (name "Net-(Q1-G)") (class "Default")
      (node (ref "Q1") (pin "1") (pinfunction "G_1") (pintype "passive"))
      (node (ref "R20") (pin "1") (pinfunction "1_1") (pintype "passive"))
      (node (ref "R21") (pin "2") (pinfunction "2_2") (pintype "passive"))
    )
    (net (code "67") (name "Net-(R15-Pad2)") (class "Default")
      (node (ref "R15") (pin "2") (pinfunction "2_2") (pintype "passive"))
      (node (ref "U1") (pin "61") (pinfunction "RESERVED_61") (pintype "passive"))
    )
    (net (code "68") (name "Net-(R16-Pad2)") (class "Default")
      (node (ref "R16") (pin "2") (pinfunction "2_2") (pintype "passive"))
      (node (ref "U1") (pin "62") (pinfunction "RESERVED_62") (pintype "passive"))
    )
    (net (code "69") (name "Net-(R23-Pad1)") (class "Default")
      (node (ref "R23") (pin "1") (pinfunction "1_1") (pintype "passive"))
      (node (ref "RJ1") (pin "12") (pinfunction "12_12") (pintype "passive"))
      (node (ref "RJ1") (pin "14") (pinfunction "14_14") (pintype "passive"))
    )
    (net (code "70") (name "Net-(R24-Pad1)") (class "Default")
      (node (ref "R24") (pin "1") (pinfunction "1_1") (pintype "passive"))
      (node (ref "RJ2") (pin "12") (pinfunction "12_12") (pintype "passive"))
      (node (ref "RJ2") (pin "14") (pinfunction "14_14") (pintype "passive"))
    )
    (net (code "71") (name "Net-(R25-Pad1)") (class "Default")
      (node (ref "R25") (pin "1") (pinfunction "1_1") (pintype "passive"))
      (node (ref "RJ5") (pin "12") (pinfunction "12_12") (pintype "passive"))
      (node (ref "RJ5") (pin "14") (pinfunction "14_14") (pintype "passive"))
    )
    (net (code "72") (name "Net-(R26-Pad1)") (class "Default")
      (node (ref "R26") (pin "1") (pinfunction "1_1") (pintype "passive"))
      (node (ref "RJ3") (pin "12") (pinfunction "12_12") (pintype "passive"))
      (node (ref "RJ3") (pin "14") (pinfunction "14_14") (pintype "passive"))
    )
    (net (code "73") (name "Net-(R27-Pad1)") (class "Default")
      (node (ref "R27") (pin "1") (pinfunction "1_1") (pintype "passive"))
      (node (ref "RJ4") (pin "12") (pinfunction "12_12") (pintype "passive"))
      (node (ref "RJ4") (pin "14") (pinfunction "14_14") (pintype "passive"))
    )
    (net (code "74") (name "Net-(U1-GPO44{slash}DIS_8051)") (class "Default")
      (node (ref "R5") (pin "2") (pinfunction "2_2") (pintype "passive"))
      (node (ref "U1") (pin "69") (pinfunction "GPO44/DIS_8051_69") (pintype "passive"))
    )
    (net (code "75") (name "Net-(U1-MDIREF)") (class "Default")
      (node (ref "R14") (pin "1") (pinfunction "1_1") (pintype "passive"))
      (node (ref "U1") (pin "37") (pinfunction "MDIREF_37") (pintype "passive"))
    )
    (net (code "76") (name "Net-(U1-PLLVDDL)") (class "Default")
      (node (ref "C8") (pin "1") (pinfunction "1_1") (pintype "passive"))
      (node (ref "R13") (pin "1") (pinfunction "1_1") (pintype "passive"))
      (node (ref "U1") (pin "15") (pinfunction "PLLVDDL_15") (pintype "passive"))
    )
    (net (code "77") (name "Net-(U1-SCK{slash}EN_EEE)") (class "Default")
      (node (ref "R12") (pin "2") (pinfunction "2_2") (pintype "passive"))
      (node (ref "U1") (pin "81") (pinfunction "SCK/EN_EEE_81") (pintype "passive"))
    )
    (net (code "78") (name "Net-(USB1-CC1)") (class "Default")
      (node (ref "R19") (pin "1") (pinfunction "1_1") (pintype "passive"))
      (node (ref "USB1") (pin "A5") (pinfunction "CC1_A5") (pintype "passive"))
    )
    (net (code "79") (name "Net-(USB1-CC2)") (class "Default")
      (node (ref "R18") (pin "1") (pinfunction "1_1") (pintype "passive"))
      (node (ref "USB1") (pin "B5") (pinfunction "CC2_B5") (pintype "passive"))
    )
    (net (code "80") (name "VCC1V") (class "Default")
      (node (ref "C10") (pin "1") (pinfunction "1_1") (pintype "passive"))
      (node (ref "C12") (pin "2") (pinfunction "2_2") (pintype "passive"))
      (node (ref "C19") (pin "1") (pinfunction "1_1") (pintype "passive"))
      (node (ref "C20") (pin "1") (pinfunction "1_1") (pintype "passive"))
      (node (ref "C21") (pin "1") (pinfunction "1_1") (pintype "passive"))
      (node (ref "C7") (pin "1") (pinfunction "1_1") (pintype "passive"))
      (node (ref "R13") (pin "2") (pinfunction "2_2") (pintype "passive"))
      (node (ref "R20") (pin "2") (pinfunction "2_2") (pintype "passive"))
      (node (ref "U1") (pin "10") (pinfunction "AVDDL_10") (pintype "passive"))
      (node (ref "U1") (pin "20") (pinfunction "AVDDL_20") (pintype "passive"))
      (node (ref "U1") (pin "30") (pinfunction "AVDDL_30") (pintype "passive"))
      (node (ref "U1") (pin "38") (pinfunction "AVDDL_38") (pintype "passive"))
      (node (ref "U1") (pin "41") (pinfunction "DVDDL_41") (pintype "passive"))
      (node (ref "U1") (pin "47") (pinfunction "AVDDL_47") (pintype "passive"))
      (node (ref "U1") (pin "53") (pinfunction "AVDDL_53") (pintype "passive"))
      (node (ref "U1") (pin "60") (pinfunction "DVDDL_60") (pintype "passive"))
      (node (ref "U1") (pin "64") (pinfunction "DVDDL_64") (pintype "passive"))
      (node (ref "U1") (pin "88") (pinfunction "AVDDL_88") (pintype "passive"))
      (node (ref "U3") (pin "2") (pinfunction "OUT_2") (pintype "passive"))
      (node (ref "U3") (pin "4") (pinfunction "OUT_4") (pintype "passive"))
    )
    (net (code "81") (name "VCC3V3") (class "Default")
      (node (ref "C11") (pin "2") (pinfunction "2_2") (pintype "passive"))
      (node (ref "C16") (pin "1") (pinfunction "1_1") (pintype "passive"))
      (node (ref "C17") (pin "1") (pinfunction "1_1") (pintype "passive"))
      (node (ref "C18") (pin "1") (pinfunction "1_1") (pintype "passive"))
      (node (ref "C6") (pin "1") (pinfunction "1_1") (pintype "passive"))
      (node (ref "C9") (pin "1") (pinfunction "1_1") (pintype "passive"))
      (node (ref "R12") (pin "1") (pinfunction "1_1") (pintype "passive"))
      (node (ref "R17") (pin "1") (pinfunction "1_1") (pintype "passive"))
      (node (ref "R22") (pin "2") (pinfunction "2_2") (pintype "passive"))
      (node (ref "R5") (pin "1") (pinfunction "1_1") (pintype "passive"))
      (node (ref "R6") (pin "1") (pinfunction "1_1") (pintype "passive"))
      (node (ref "R7") (pin "1") (pinfunction "1_1") (pintype "passive"))
      (node (ref "U1") (pin "25") (pinfunction "AVDDH_25") (pintype "passive"))
      (node (ref "U1") (pin "35") (pinfunction "AVDDH_35") (pintype "passive"))
      (node (ref "U1") (pin "40") (pinfunction "AVDDH_40") (pintype "passive"))
      (node (ref "U1") (pin "42") (pinfunction "AVDDH_42") (pintype "passive"))
      (node (ref "U1") (pin "5") (pinfunction "AVDDH_5") (pintype "passive"))
      (node (ref "U1") (pin "52") (pinfunction "AVDDH_52") (pintype "passive"))
      (node (ref "U1") (pin "63") (pinfunction "DVDDIO_63") (pintype "passive"))
      (node (ref "U1") (pin "77") (pinfunction "AVDDH_77") (pintype "passive"))
      (node (ref "U1") (pin "83") (pinfunction "AVDDH_83") (pintype "passive"))
      (node (ref "U2") (pin "2") (pinfunction "OUT_2") (pintype "passive"))
      (node (ref "U3") (pin "3") (pinfunction "IN_3") (pintype "passive"))
    )
    (net (code "82") (name "VCC5V") (class "Default")
      (node (ref "F1") (pin "2") (pinfunction "2_2") (pintype "passive"))
      (node (ref "F2") (pin "2") (pinfunction "2_2") (pintype "passive"))
      (node (ref "H1") (pin "7") (pinfunction "7_7") (pintype "passive"))
      (node (ref "U2") (pin "3") (pinfunction "IN_3") (pintype "passive"))
    )
    (net (code "83") (name "unconnected-(H1-Pad2)") (class "Default")
      (node (ref "H1") (pin "2") (pinfunction "2_2") (pintype "passive"))
    )
    (net (code "84") (name "unconnected-(H1-Pad4)") (class "Default")
      (node (ref "H1") (pin "4") (pinfunction "4_4") (pintype "passive"))
    )
    (net (code "85") (name "unconnected-(H1-Pad6)") (class "Default")
      (node (ref "H1") (pin "6") (pinfunction "6_6") (pintype "passive"))
    )
    (net (code "86") (name "unconnected-(H1-Pad8)") (class "Default")
      (node (ref "H1") (pin "8") (pinfunction "8_8") (pintype "passive"))
    )
    (net (code "87") (name "unconnected-(U1-GPIO04{slash}SPIF_CLK-Pad56)") (class "Default")
      (node (ref "U1") (pin "56") (pinfunction "GPIO04/SPIF_CLK_56") (pintype "passive+no_connect"))
    )
    (net (code "88") (name "unconnected-(U1-GPIO05{slash}SPIF_D0-Pad57)") (class "Default")
      (node (ref "U1") (pin "57") (pinfunction "GPIO05/SPIF_D0_57") (pintype "passive+no_connect"))
    )
    (net (code "89") (name "unconnected-(U1-GPIO09{slash}SPIF_D1-Pad58)") (class "Default")
      (node (ref "U1") (pin "58") (pinfunction "GPIO09/SPIF_D1_58") (pintype "passive+no_connect"))
    )
    (net (code "90") (name "unconnected-(U1-GPIO10{slash}SPIF_CS-Pad59)") (class "Default")
      (node (ref "U1") (pin "59") (pinfunction "GPIO10/SPIF_CS_59") (pintype "passive+no_connect"))
    )
    (net (code "91") (name "unconnected-(U1-NC-Pad76)") (class "Default")
      (node (ref "U1") (pin "76") (pinfunction "NC_76") (pintype "passive+no_connect"))
    )
    (net (code "92") (name "unconnected-(U1-RTT1-Pad39)") (class "Default")
      (node (ref "U1") (pin "39") (pinfunction "RTT1_39") (pintype "passive+no_connect"))
    )
    (net (code "93") (name "unconnected-(U1-SDA-Pad82)") (class "Default")
      (node (ref "U1") (pin "82") (pinfunction "SDA_82") (pintype "passive+no_connect"))
    )
  )
)
